# tl100-4-driver_sch-pcb.net
KiCad netlist of a schematic drawn in EAGLE
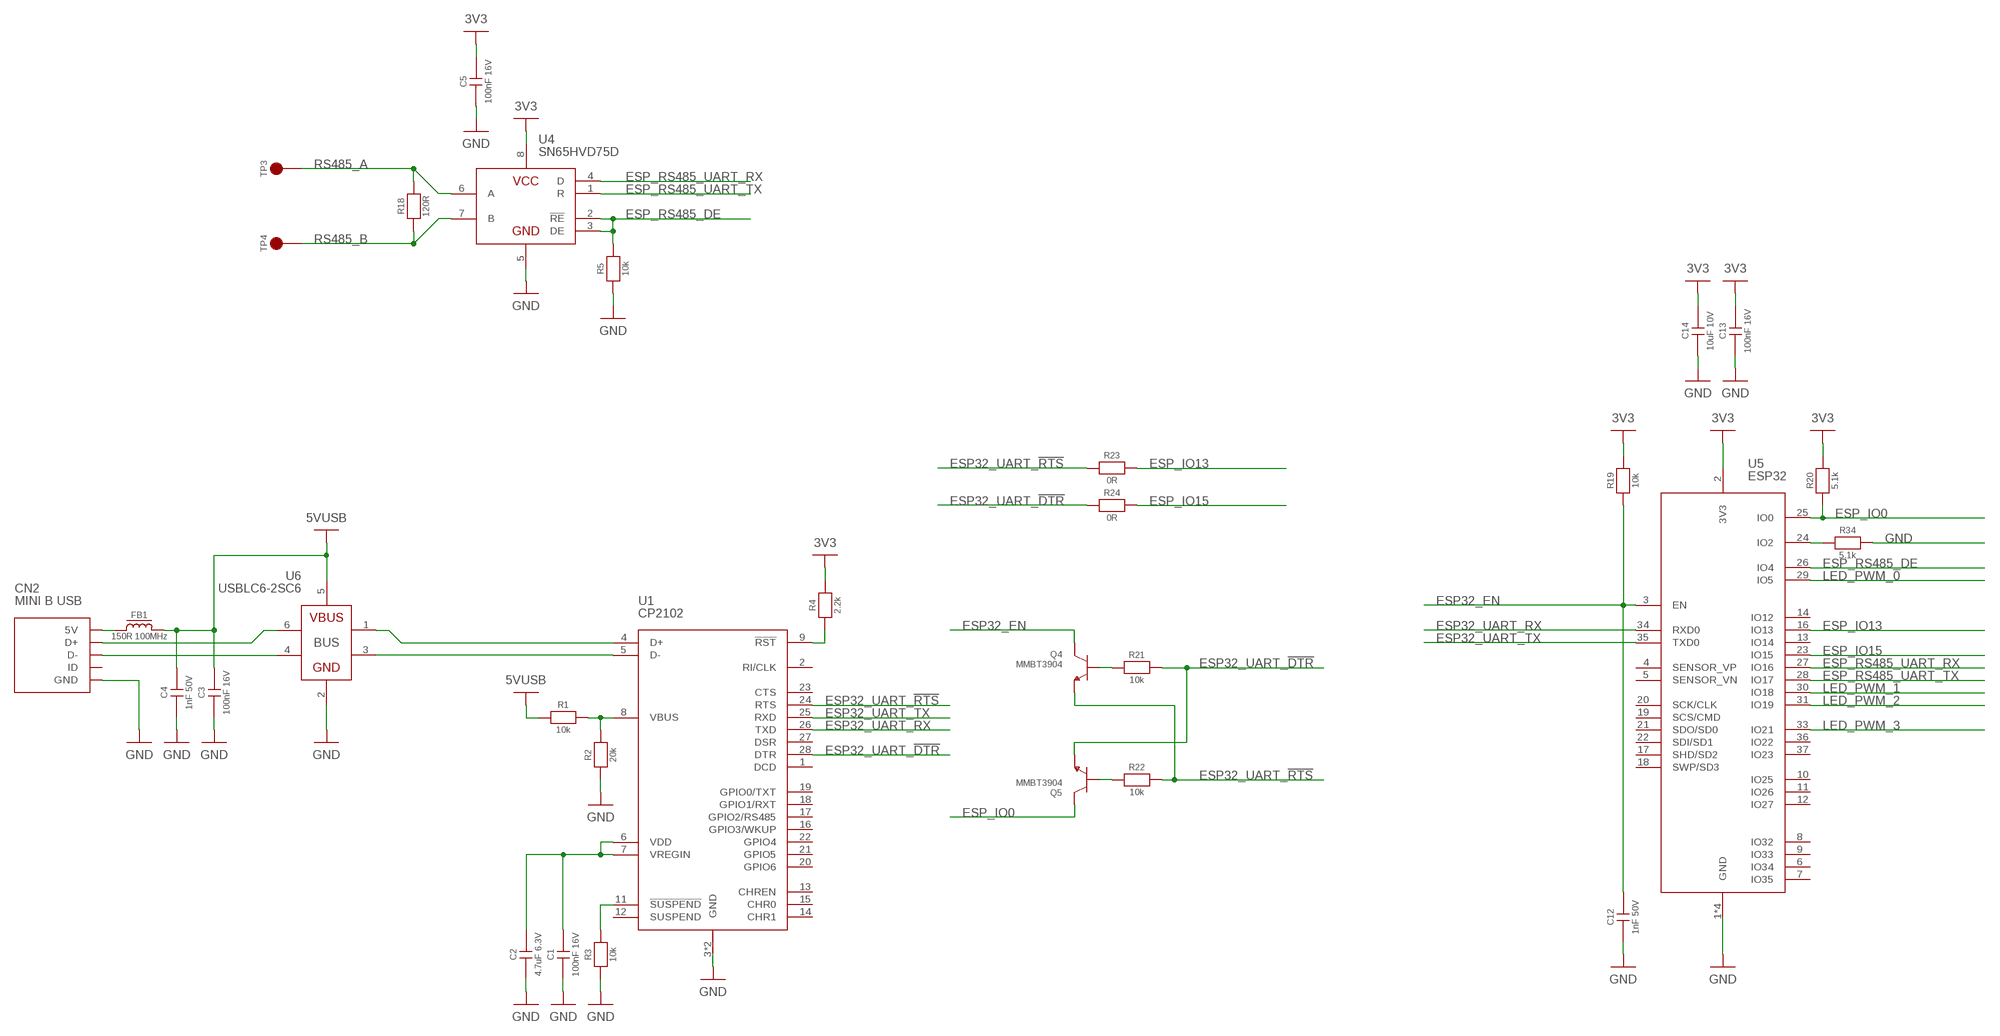
[diagram p0: schematic, sheet 1]
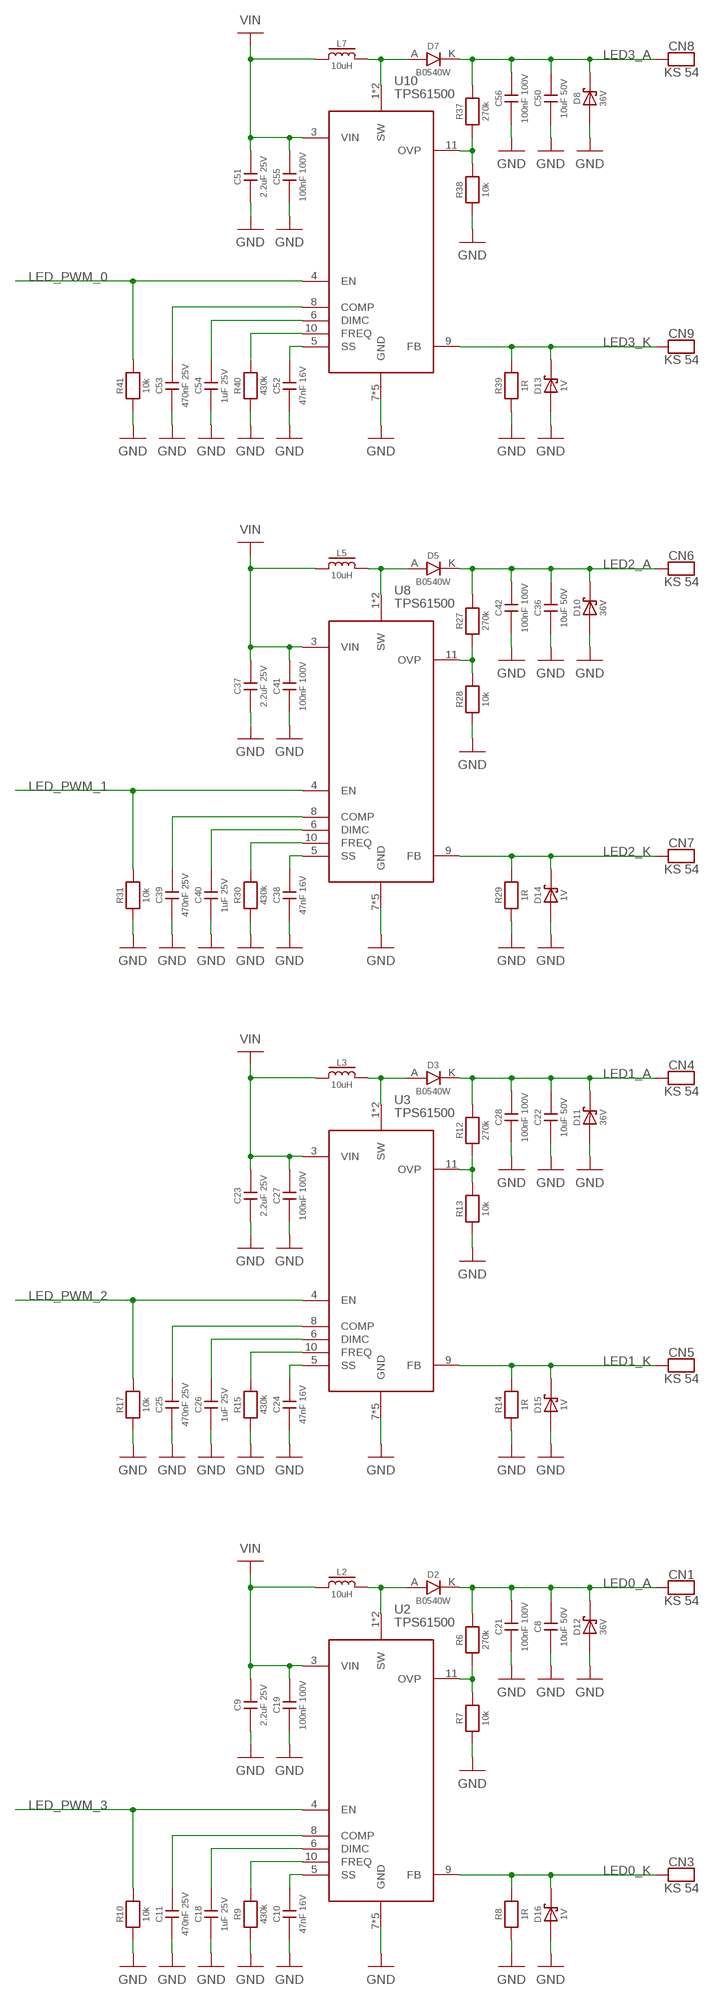
[diagram p1: schematic, sheet 2]
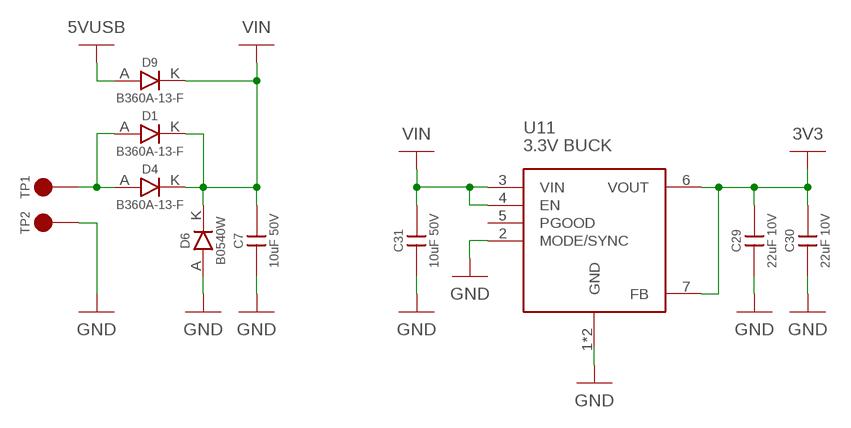
[diagram p2: schematic, sheet 3]
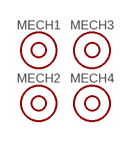
[diagram p3: schematic, sheet 4]

(export (version "E")
  (design (tool "Eeschema 10.0.6"))
  (components
    (comp (ref "MECH1")
      (value "6mm x 3mm")
      (footprint "eagle-import:MOUNTHOLE_6X3")
      (libsource (lib "eagle-import") (part "MOUNTHOLE"))
    )
    (comp (ref "MECH2")
      (value "6mm x 3mm")
      (footprint "eagle-import:MOUNTHOLE_6X3")
      (libsource (lib "eagle-import") (part "MOUNTHOLE"))
    )
    (comp (ref "MECH3")
      (value "6mm x 3mm")
      (footprint "eagle-import:MOUNTHOLE_6X3")
      (libsource (lib "eagle-import") (part "MOUNTHOLE"))
    )
    (comp (ref "MECH4")
      (value "6mm x 3mm")
      (footprint "eagle-import:MOUNTHOLE_6X3")
      (libsource (lib "eagle-import") (part "MOUNTHOLE"))
    )
    (comp (ref "C1")
      (value "100nF 16V")
      (footprint "eagle-import:0603")
      (libsource (lib "eagle-import") (part "CL10B104KO8WPNC"))
    )
    (comp (ref "C2")
      (value "4.7uF 6.3V")
      (footprint "eagle-import:0603")
      (libsource (lib "eagle-import") (part "GRM188R60J475ME19D"))
    )
    (comp (ref "C3")
      (value "100nF 16V")
      (footprint "eagle-import:0603")
      (libsource (lib "eagle-import") (part "CL10B104KO8WPNC"))
    )
    (comp (ref "C4")
      (value "1nF 50V")
      (footprint "eagle-import:0603")
      (libsource (lib "eagle-import") (part "CL10B102KB8NNNC"))
    )
    (comp (ref "C5")
      (value "100nF 16V")
      (footprint "eagle-import:0603")
      (libsource (lib "eagle-import") (part "CL10B104KO8WPNC"))
    )
    (comp (ref "C12")
      (value "1nF 50V")
      (footprint "eagle-import:0603")
      (libsource (lib "eagle-import") (part "CL10B102KB8NNNC"))
    )
    (comp (ref "C13")
      (value "100nF 16V")
      (footprint "eagle-import:0603")
      (libsource (lib "eagle-import") (part "CL10B104KO8WPNC"))
    )
    (comp (ref "C14")
      (value "10uF 10V")
      (footprint "eagle-import:0603")
      (libsource (lib "eagle-import") (part "GRM188R61A106KE69D"))
    )
    (comp (ref "CN2")
      (value "MINI B USB")
      (footprint "eagle-import:MUSB-05-S-B-SM-A")
      (libsource (lib "eagle-import") (part "MUSB-05-S-B-SM-A"))
    )
    (comp (ref "FB1")
      (value "150R 100MHz")
      (footprint "eagle-import:1206")
      (libsource (lib "eagle-import") (part "ILB1206ER151V"))
    )
    (comp (ref "Q4")
      (value "MMBT3904")
      (footprint "eagle-import:SOT23-3")
      (libsource (lib "eagle-import") (part "MMBT3904-7-F"))
    )
    (comp (ref "Q5")
      (value "MMBT3904")
      (footprint "eagle-import:SOT23-3")
      (libsource (lib "eagle-import") (part "MMBT3904-7-F"))
    )
    (comp (ref "R1")
      (value "10k")
      (footprint "eagle-import:0603")
      (libsource (lib "eagle-import") (part "ERJ3EKF1002V"))
    )
    (comp (ref "R2")
      (value "20k")
      (footprint "eagle-import:0603")
      (libsource (lib "eagle-import") (part "ERJ3EKF2002V"))
    )
    (comp (ref "R3")
      (value "10k")
      (footprint "eagle-import:0603")
      (libsource (lib "eagle-import") (part "ERJ3EKF1002V"))
    )
    (comp (ref "R4")
      (value "2.2k")
      (footprint "eagle-import:0603")
      (libsource (lib "eagle-import") (part "ERJ3EKF2201V"))
    )
    (comp (ref "R5")
      (value "10k")
      (footprint "eagle-import:0603")
      (libsource (lib "eagle-import") (part "ERJ3EKF1002V"))
    )
    (comp (ref "R18")
      (value "120R")
      (footprint "eagle-import:0603")
      (libsource (lib "eagle-import") (part "ERJ3EKF1200V"))
    )
    (comp (ref "R19")
      (value "10k")
      (footprint "eagle-import:0603")
      (libsource (lib "eagle-import") (part "ERJ3EKF1002V"))
    )
    (comp (ref "R20")
      (value "5.1k")
      (footprint "eagle-import:0603")
      (libsource (lib "eagle-import") (part "ERJ3EKF5101V"))
    )
    (comp (ref "R21")
      (value "10k")
      (footprint "eagle-import:0603")
      (libsource (lib "eagle-import") (part "ERJ3EKF1002V"))
    )
    (comp (ref "R22")
      (value "10k")
      (footprint "eagle-import:0603")
      (libsource (lib "eagle-import") (part "ERJ3EKF1002V"))
    )
    (comp (ref "R23")
      (value "0R")
      (footprint "eagle-import:0603")
      (libsource (lib "eagle-import") (part "CRCW06030000Z0EA"))
    )
    (comp (ref "R24")
      (value "0R")
      (footprint "eagle-import:0603")
      (libsource (lib "eagle-import") (part "CRCW06030000Z0EA"))
    )
    (comp (ref "R34")
      (value "5.1k")
      (footprint "eagle-import:0603")
      (libsource (lib "eagle-import") (part "ERJ3EKF5101V"))
    )
    (comp (ref "TP3")
      (value "2MM_TEST_POINT")
      (footprint "eagle-import:2MM_TEST_PAD")
      (libsource (lib "eagle-import") (part "2MM_TEST_POINT"))
    )
    (comp (ref "TP4")
      (value "2MM_TEST_POINT")
      (footprint "eagle-import:2MM_TEST_PAD")
      (libsource (lib "eagle-import") (part "2MM_TEST_POINT"))
    )
    (comp (ref "U1")
      (value "CP2102")
      (footprint "eagle-import:QFN28")
      (libsource (lib "eagle-import") (part "CP2102N-A01-GQFN28"))
    )
    (comp (ref "U4")
      (value "SN65HVD75D")
      (footprint "eagle-import:SO8")
      (libsource (lib "eagle-import") (part "SN65HVD75D"))
    )
    (comp (ref "U5")
      (value "ESP32")
      (footprint "eagle-import:ESP32-WROOM-32D")
      (libsource (lib "eagle-import") (part "ESP32-WROOM-32D"))
    )
    (comp (ref "U6")
      (value "USBLC6-2SC6")
      (footprint "eagle-import:SOT23-6")
      (libsource (lib "eagle-import") (part "USBLC6-2SC6"))
    )
    (comp (ref "C7")
      (value "10uF 50V")
      (footprint "eagle-import:1210")
      (libsource (lib "eagle-import") (part "C3225X7S1H106M250AB"))
    )
    (comp (ref "C29")
      (value "22uF 10V")
      (footprint "eagle-import:1206")
      (libsource (lib "eagle-import") (part "CL31B226MPHNNNE"))
    )
    (comp (ref "C30")
      (value "22uF 10V")
      (footprint "eagle-import:1206")
      (libsource (lib "eagle-import") (part "CL31B226MPHNNNE"))
    )
    (comp (ref "C31")
      (value "10uF 50V")
      (footprint "eagle-import:1210")
      (libsource (lib "eagle-import") (part "C3225X7S1H106M250AB"))
    )
    (comp (ref "D1")
      (value "B360A-13-F")
      (footprint "eagle-import:DO214AC")
      (libsource (lib "eagle-import") (part "B360A-13-F"))
    )
    (comp (ref "D4")
      (value "B360A-13-F")
      (footprint "eagle-import:DO214AC")
      (libsource (lib "eagle-import") (part "B360A-13-F"))
    )
    (comp (ref "D6")
      (value "B0540W")
      (footprint "eagle-import:SOD-123")
      (libsource (lib "eagle-import") (part "B0540W"))
    )
    (comp (ref "D9")
      (value "B360A-13-F")
      (footprint "eagle-import:DO214AC")
      (libsource (lib "eagle-import") (part "B360A-13-F"))
    )
    (comp (ref "TP1")
      (value "2MM_TEST_POINT")
      (footprint "eagle-import:2MM_TEST_PAD")
      (libsource (lib "eagle-import") (part "2MM_TEST_POINT"))
    )
    (comp (ref "TP2")
      (value "2MM_TEST_POINT")
      (footprint "eagle-import:2MM_TEST_PAD")
      (libsource (lib "eagle-import") (part "2MM_TEST_POINT"))
    )
    (comp (ref "U11")
      (value "3.3V BUCK")
      (footprint "eagle-import:TI_MICROSIP_10")
      (libsource (lib "eagle-import") (part "LMZM23600V3SILT"))
    )
    (comp (ref "C8")
      (value "10uF 50V")
      (footprint "eagle-import:1210")
      (libsource (lib "eagle-import") (part "C3225X7S1H106M250AB"))
    )
    (comp (ref "C9")
      (value "2.2uF 25V")
      (footprint "eagle-import:0603")
      (libsource (lib "eagle-import") (part "GRM188R61E225KA12D"))
    )
    (comp (ref "C10")
      (value "47nF 16V")
      (footprint "eagle-import:0603")
      (libsource (lib "eagle-import") (part "CL10B473KO8NNNC"))
    )
    (comp (ref "C11")
      (value "470nF 25V")
      (footprint "eagle-import:0603")
      (libsource (lib "eagle-import") (part "GRM188R71E474KA12D"))
    )
    (comp (ref "C18")
      (value "1uF 25V")
      (footprint "eagle-import:0603")
      (libsource (lib "eagle-import") (part "CL10A105KA8NNNC"))
    )
    (comp (ref "C19")
      (value "100nF 100V")
      (footprint "eagle-import:0603")
      (libsource (lib "eagle-import") (part "06031C104KAT2A"))
    )
    (comp (ref "C21")
      (value "100nF 100V")
      (footprint "eagle-import:0603")
      (libsource (lib "eagle-import") (part "06031C104KAT2A"))
    )
    (comp (ref "C22")
      (value "10uF 50V")
      (footprint "eagle-import:1210")
      (libsource (lib "eagle-import") (part "C3225X7S1H106M250AB"))
    )
    (comp (ref "C23")
      (value "2.2uF 25V")
      (footprint "eagle-import:0603")
      (libsource (lib "eagle-import") (part "GRM188R61E225KA12D"))
    )
    (comp (ref "C24")
      (value "47nF 16V")
      (footprint "eagle-import:0603")
      (libsource (lib "eagle-import") (part "CL10B473KO8NNNC"))
    )
    (comp (ref "C25")
      (value "470nF 25V")
      (footprint "eagle-import:0603")
      (libsource (lib "eagle-import") (part "GRM188R71E474KA12D"))
    )
    (comp (ref "C26")
      (value "1uF 25V")
      (footprint "eagle-import:0603")
      (libsource (lib "eagle-import") (part "CL10A105KA8NNNC"))
    )
    (comp (ref "C27")
      (value "100nF 100V")
      (footprint "eagle-import:0603")
      (libsource (lib "eagle-import") (part "06031C104KAT2A"))
    )
    (comp (ref "C28")
      (value "100nF 100V")
      (footprint "eagle-import:0603")
      (libsource (lib "eagle-import") (part "06031C104KAT2A"))
    )
    (comp (ref "C36")
      (value "10uF 50V")
      (footprint "eagle-import:1210")
      (libsource (lib "eagle-import") (part "C3225X7S1H106M250AB"))
    )
    (comp (ref "C37")
      (value "2.2uF 25V")
      (footprint "eagle-import:0603")
      (libsource (lib "eagle-import") (part "GRM188R61E225KA12D"))
    )
    (comp (ref "C38")
      (value "47nF 16V")
      (footprint "eagle-import:0603")
      (libsource (lib "eagle-import") (part "CL10B473KO8NNNC"))
    )
    (comp (ref "C39")
      (value "470nF 25V")
      (footprint "eagle-import:0603")
      (libsource (lib "eagle-import") (part "GRM188R71E474KA12D"))
    )
    (comp (ref "C40")
      (value "1uF 25V")
      (footprint "eagle-import:0603")
      (libsource (lib "eagle-import") (part "CL10A105KA8NNNC"))
    )
    (comp (ref "C41")
      (value "100nF 100V")
      (footprint "eagle-import:0603")
      (libsource (lib "eagle-import") (part "06031C104KAT2A"))
    )
    (comp (ref "C42")
      (value "100nF 100V")
      (footprint "eagle-import:0603")
      (libsource (lib "eagle-import") (part "06031C104KAT2A"))
    )
    (comp (ref "C50")
      (value "10uF 50V")
      (footprint "eagle-import:1210")
      (libsource (lib "eagle-import") (part "C3225X7S1H106M250AB"))
    )
    (comp (ref "C51")
      (value "2.2uF 25V")
      (footprint "eagle-import:0603")
      (libsource (lib "eagle-import") (part "GRM188R61E225KA12D"))
    )
    (comp (ref "C52")
      (value "47nF 16V")
      (footprint "eagle-import:0603")
      (libsource (lib "eagle-import") (part "CL10B473KO8NNNC"))
    )
    (comp (ref "C53")
      (value "470nF 25V")
      (footprint "eagle-import:0603")
      (libsource (lib "eagle-import") (part "GRM188R71E474KA12D"))
    )
    (comp (ref "C54")
      (value "1uF 25V")
      (footprint "eagle-import:0603")
      (libsource (lib "eagle-import") (part "CL10A105KA8NNNC"))
    )
    (comp (ref "C55")
      (value "100nF 100V")
      (footprint "eagle-import:0603")
      (libsource (lib "eagle-import") (part "06031C104KAT2A"))
    )
    (comp (ref "C56")
      (value "100nF 100V")
      (footprint "eagle-import:0603")
      (libsource (lib "eagle-import") (part "06031C104KAT2A"))
    )
    (comp (ref "CN1")
      (value "KS 54")
      (footprint "eagle-import:KEYSTONE_54")
      (libsource (lib "eagle-import") (part "KEYSTONE_54"))
    )
    (comp (ref "CN3")
      (value "KS 54")
      (footprint "eagle-import:KEYSTONE_54")
      (libsource (lib "eagle-import") (part "KEYSTONE_54"))
    )
    (comp (ref "CN4")
      (value "KS 54")
      (footprint "eagle-import:KEYSTONE_54")
      (libsource (lib "eagle-import") (part "KEYSTONE_54"))
    )
    (comp (ref "CN5")
      (value "KS 54")
      (footprint "eagle-import:KEYSTONE_54")
      (libsource (lib "eagle-import") (part "KEYSTONE_54"))
    )
    (comp (ref "CN6")
      (value "KS 54")
      (footprint "eagle-import:KEYSTONE_54")
      (libsource (lib "eagle-import") (part "KEYSTONE_54"))
    )
    (comp (ref "CN7")
      (value "KS 54")
      (footprint "eagle-import:KEYSTONE_54")
      (libsource (lib "eagle-import") (part "KEYSTONE_54"))
    )
    (comp (ref "CN8")
      (value "KS 54")
      (footprint "eagle-import:KEYSTONE_54")
      (libsource (lib "eagle-import") (part "KEYSTONE_54"))
    )
    (comp (ref "CN9")
      (value "KS 54")
      (footprint "eagle-import:KEYSTONE_54")
      (libsource (lib "eagle-import") (part "KEYSTONE_54"))
    )
    (comp (ref "D2")
      (value "B0540W")
      (footprint "eagle-import:SOD-123")
      (libsource (lib "eagle-import") (part "B0540W"))
    )
    (comp (ref "D3")
      (value "B0540W")
      (footprint "eagle-import:SOD-123")
      (libsource (lib "eagle-import") (part "B0540W"))
    )
    (comp (ref "D5")
      (value "B0540W")
      (footprint "eagle-import:SOD-123")
      (libsource (lib "eagle-import") (part "B0540W"))
    )
    (comp (ref "D7")
      (value "B0540W")
      (footprint "eagle-import:SOD-123")
      (libsource (lib "eagle-import") (part "B0540W"))
    )
    (comp (ref "D8")
      (value "36V")
      (footprint "eagle-import:SOT23-3")
      (libsource (lib "eagle-import") (part "GSOT36-HE3-08"))
    )
    (comp (ref "D10")
      (value "36V")
      (footprint "eagle-import:SOT23-3")
      (libsource (lib "eagle-import") (part "GSOT36-HE3-08"))
    )
    (comp (ref "D11")
      (value "36V")
      (footprint "eagle-import:SOT23-3")
      (libsource (lib "eagle-import") (part "GSOT36-HE3-08"))
    )
    (comp (ref "D12")
      (value "36V")
      (footprint "eagle-import:SOT23-3")
      (libsource (lib "eagle-import") (part "GSOT36-HE3-08"))
    )
    (comp (ref "D13")
      (value "1V")
      (footprint "eagle-import:SC-79")
      (libsource (lib "eagle-import") (part "VESD01C1-02VHG3-08"))
    )
    (comp (ref "D14")
      (value "1V")
      (footprint "eagle-import:SC-79")
      (libsource (lib "eagle-import") (part "VESD01C1-02VHG3-08"))
    )
    (comp (ref "D15")
      (value "1V")
      (footprint "eagle-import:SC-79")
      (libsource (lib "eagle-import") (part "VESD01C1-02VHG3-08"))
    )
    (comp (ref "D16")
      (value "1V")
      (footprint "eagle-import:SC-79")
      (libsource (lib "eagle-import") (part "VESD01C1-02VHG3-08"))
    )
    (comp (ref "L2")
      (value "10uH")
      (footprint "eagle-import:SRN6045")
      (libsource (lib "eagle-import") (part "SRN6045-100M"))
    )
    (comp (ref "L3")
      (value "10uH")
      (footprint "eagle-import:SRN6045")
      (libsource (lib "eagle-import") (part "SRN6045-100M"))
    )
    (comp (ref "L5")
      (value "10uH")
      (footprint "eagle-import:SRN6045")
      (libsource (lib "eagle-import") (part "SRN6045-100M"))
    )
    (comp (ref "L7")
      (value "10uH")
      (footprint "eagle-import:SRN6045")
      (libsource (lib "eagle-import") (part "SRN6045-100M"))
    )
    (comp (ref "R6")
      (value "270k")
      (footprint "eagle-import:0603")
      (libsource (lib "eagle-import") (part "ERJ3EKF2703V"))
    )
    (comp (ref "R7")
      (value "10k")
      (footprint "eagle-import:0603")
      (libsource (lib "eagle-import") (part "ERJ3EKF1002V"))
    )
    (comp (ref "R8")
      (value "1R")
      (footprint "eagle-import:1206")
      (libsource (lib "eagle-import") (part "CRCW12061R00FKEA"))
    )
    (comp (ref "R9")
      (value "430k")
      (footprint "eagle-import:0603")
      (libsource (lib "eagle-import") (part "ERJ3EKF4303V"))
    )
    (comp (ref "R10")
      (value "10k")
      (footprint "eagle-import:0603")
      (libsource (lib "eagle-import") (part "ERJ3EKF1002V"))
    )
    (comp (ref "R12")
      (value "270k")
      (footprint "eagle-import:0603")
      (libsource (lib "eagle-import") (part "ERJ3EKF2703V"))
    )
    (comp (ref "R13")
      (value "10k")
      (footprint "eagle-import:0603")
      (libsource (lib "eagle-import") (part "ERJ3EKF1002V"))
    )
    (comp (ref "R14")
      (value "1R")
      (footprint "eagle-import:1206")
      (libsource (lib "eagle-import") (part "CRCW12061R00FKEA"))
    )
    (comp (ref "R15")
      (value "430k")
      (footprint "eagle-import:0603")
      (libsource (lib "eagle-import") (part "ERJ3EKF4303V"))
    )
    (comp (ref "R17")
      (value "10k")
      (footprint "eagle-import:0603")
      (libsource (lib "eagle-import") (part "ERJ3EKF1002V"))
    )
    (comp (ref "R27")
      (value "270k")
      (footprint "eagle-import:0603")
      (libsource (lib "eagle-import") (part "ERJ3EKF2703V"))
    )
    (comp (ref "R28")
      (value "10k")
      (footprint "eagle-import:0603")
      (libsource (lib "eagle-import") (part "ERJ3EKF1002V"))
    )
    (comp (ref "R29")
      (value "1R")
      (footprint "eagle-import:1206")
      (libsource (lib "eagle-import") (part "CRCW12061R00FKEA"))
    )
    (comp (ref "R30")
      (value "430k")
      (footprint "eagle-import:0603")
      (libsource (lib "eagle-import") (part "ERJ3EKF4303V"))
    )
    (comp (ref "R31")
      (value "10k")
      (footprint "eagle-import:0603")
      (libsource (lib "eagle-import") (part "ERJ3EKF1002V"))
    )
    (comp (ref "R37")
      (value "270k")
      (footprint "eagle-import:0603")
      (libsource (lib "eagle-import") (part "ERJ3EKF2703V"))
    )
    (comp (ref "R38")
      (value "10k")
      (footprint "eagle-import:0603")
      (libsource (lib "eagle-import") (part "ERJ3EKF1002V"))
    )
    (comp (ref "R39")
      (value "1R")
      (footprint "eagle-import:1206")
      (libsource (lib "eagle-import") (part "CRCW12061R00FKEA"))
    )
    (comp (ref "R40")
      (value "430k")
      (footprint "eagle-import:0603")
      (libsource (lib "eagle-import") (part "ERJ3EKF4303V"))
    )
    (comp (ref "R41")
      (value "10k")
      (footprint "eagle-import:0603")
      (libsource (lib "eagle-import") (part "ERJ3EKF1002V"))
    )
    (comp (ref "U2")
      (value "TPS61500")
      (footprint "eagle-import:HTSSOP14-4.5")
      (libsource (lib "eagle-import") (part "TPS61500"))
    )
    (comp (ref "U3")
      (value "TPS61500")
      (footprint "eagle-import:HTSSOP14-4.5")
      (libsource (lib "eagle-import") (part "TPS61500"))
    )
    (comp (ref "U8")
      (value "TPS61500")
      (footprint "eagle-import:HTSSOP14-4.5")
      (libsource (lib "eagle-import") (part "TPS61500"))
    )
    (comp (ref "U10")
      (value "TPS61500")
      (footprint "eagle-import:HTSSOP14-4.5")
      (libsource (lib "eagle-import") (part "TPS61500"))
    )
  )
  (nets
    (net (code "1") (name "3V3") (class "Default")
      (node (ref "C13") (pin "2") (pinfunction "2_2") (pintype "bidirectional"))
      (node (ref "C14") (pin "2") (pinfunction "2_2") (pintype "bidirectional"))
      (node (ref "C29") (pin "2") (pinfunction "2_2") (pintype "bidirectional"))
      (node (ref "C30") (pin "2") (pinfunction "2_2") (pintype "bidirectional"))
      (node (ref "C5") (pin "2") (pinfunction "2_2") (pintype "bidirectional"))
      (node (ref "R19") (pin "2") (pinfunction "2_2") (pintype "bidirectional"))
      (node (ref "R20") (pin "2") (pinfunction "2_2") (pintype "bidirectional"))
      (node (ref "R4") (pin "2") (pinfunction "2_2") (pintype "bidirectional"))
      (node (ref "U11") (pin "6") (pinfunction "VOUT_6") (pintype "bidirectional"))
      (node (ref "U11") (pin "7") (pinfunction "FB_7") (pintype "bidirectional"))
      (node (ref "U4") (pin "8") (pinfunction "VCC_8") (pintype "bidirectional"))
      (node (ref "U5") (pin "2") (pinfunction "3V3_2") (pintype "bidirectional"))
    )
    (net (code "2") (name "5VUSB") (class "Default")
      (node (ref "C3") (pin "2") (pinfunction "2_2") (pintype "bidirectional"))
      (node (ref "C4") (pin "2") (pinfunction "2_2") (pintype "bidirectional"))
      (node (ref "D9") (pin "A") (pinfunction "A_A") (pintype "bidirectional"))
      (node (ref "FB1") (pin "2") (pinfunction "2_2") (pintype "bidirectional"))
      (node (ref "R1") (pin "1") (pinfunction "1_1") (pintype "bidirectional"))
      (node (ref "U6") (pin "5") (pinfunction "VBUS_5") (pintype "bidirectional"))
    )
    (net (code "3") (name "ESP32_EN") (class "Default")
      (node (ref "C12") (pin "2") (pinfunction "2_2") (pintype "bidirectional"))
      (node (ref "Q4") (pin "2") (pinfunction "C_2") (pintype "bidirectional"))
      (node (ref "R19") (pin "1") (pinfunction "1_1") (pintype "bidirectional"))
      (node (ref "U5") (pin "3") (pinfunction "EN_3") (pintype "bidirectional"))
    )
    (net (code "4") (name "ESP32_UART_RX") (class "Default")
      (node (ref "U1") (pin "26") (pinfunction "TXD_26") (pintype "bidirectional"))
      (node (ref "U5") (pin "34") (pinfunction "RXD0_34") (pintype "bidirectional"))
    )
    (net (code "5") (name "ESP32_UART_TX") (class "Default")
      (node (ref "U1") (pin "25") (pinfunction "RXD_25") (pintype "bidirectional"))
      (node (ref "U5") (pin "35") (pinfunction "TXD0_35") (pintype "bidirectional"))
    )
    (net (code "6") (name "ESP32_UART_~{DTR}") (class "Default")
      (node (ref "Q5") (pin "3") (pinfunction "E_3") (pintype "bidirectional"))
      (node (ref "R21") (pin "2") (pinfunction "2_2") (pintype "bidirectional"))
      (node (ref "R24") (pin "1") (pinfunction "1_1") (pintype "bidirectional"))
      (node (ref "U1") (pin "28") (pinfunction "DTR_28") (pintype "bidirectional"))
    )
    (net (code "7") (name "ESP32_UART_~{RTS}") (class "Default")
      (node (ref "Q4") (pin "3") (pinfunction "E_3") (pintype "bidirectional"))
      (node (ref "R22") (pin "2") (pinfunction "2_2") (pintype "bidirectional"))
      (node (ref "R23") (pin "1") (pinfunction "1_1") (pintype "bidirectional"))
      (node (ref "U1") (pin "24") (pinfunction "RTS_24") (pintype "bidirectional"))
    )
    (net (code "8") (name "ESP_IO0") (class "Default")
      (node (ref "Q5") (pin "2") (pinfunction "C_2") (pintype "bidirectional"))
      (node (ref "R20") (pin "1") (pinfunction "1_1") (pintype "bidirectional"))
      (node (ref "U5") (pin "25") (pinfunction "IO0_25") (pintype "bidirectional"))
    )
    (net (code "9") (name "ESP_IO13") (class "Default")
      (node (ref "R23") (pin "2") (pinfunction "2_2") (pintype "bidirectional"))
      (node (ref "U5") (pin "16") (pinfunction "IO13_16") (pintype "bidirectional"))
    )
    (net (code "10") (name "ESP_IO15") (class "Default")
      (node (ref "R24") (pin "2") (pinfunction "2_2") (pintype "bidirectional"))
      (node (ref "U5") (pin "23") (pinfunction "IO15_23") (pintype "bidirectional"))
    )
    (net (code "11") (name "ESP_RS485_DE") (class "Default")
      (node (ref "R5") (pin "2") (pinfunction "2_2") (pintype "bidirectional"))
      (node (ref "U4") (pin "2") (pinfunction "~{RE}_2") (pintype "bidirectional"))
      (node (ref "U4") (pin "3") (pinfunction "DE_3") (pintype "bidirectional"))
      (node (ref "U5") (pin "26") (pinfunction "IO4_26") (pintype "bidirectional"))
    )
    (net (code "12") (name "ESP_RS485_UART_RX") (class "Default")
      (node (ref "U4") (pin "4") (pinfunction "D_4") (pintype "bidirectional"))
      (node (ref "U5") (pin "27") (pinfunction "IO16_27") (pintype "bidirectional"))
    )
    (net (code "13") (name "ESP_RS485_UART_TX") (class "Default")
      (node (ref "U4") (pin "1") (pinfunction "R_1") (pintype "bidirectional"))
      (node (ref "U5") (pin "28") (pinfunction "IO17_28") (pintype "bidirectional"))
    )
    (net (code "14") (name "GND") (class "Default")
      (node (ref "C1") (pin "1") (pinfunction "1_1") (pintype "bidirectional"))
      (node (ref "C10") (pin "1") (pinfunction "1_1") (pintype "bidirectional"))
      (node (ref "C11") (pin "1") (pinfunction "1_1") (pintype "bidirectional"))
      (node (ref "C12") (pin "1") (pinfunction "1_1") (pintype "bidirectional"))
      (node (ref "C13") (pin "1") (pinfunction "1_1") (pintype "bidirectional"))
      (node (ref "C14") (pin "1") (pinfunction "1_1") (pintype "bidirectional"))
      (node (ref "C18") (pin "1") (pinfunction "1_1") (pintype "bidirectional"))
      (node (ref "C19") (pin "1") (pinfunction "1_1") (pintype "bidirectional"))
      (node (ref "C2") (pin "1") (pinfunction "1_1") (pintype "bidirectional"))
      (node (ref "C21") (pin "1") (pinfunction "1_1") (pintype "bidirectional"))
      (node (ref "C22") (pin "1") (pinfunction "1_1") (pintype "bidirectional"))
      (node (ref "C23") (pin "1") (pinfunction "1_1") (pintype "bidirectional"))
      (node (ref "C24") (pin "1") (pinfunction "1_1") (pintype "bidirectional"))
      (node (ref "C25") (pin "1") (pinfunction "1_1") (pintype "bidirectional"))
      (node (ref "C26") (pin "1") (pinfunction "1_1") (pintype "bidirectional"))
      (node (ref "C27") (pin "1") (pinfunction "1_1") (pintype "bidirectional"))
      (node (ref "C28") (pin "1") (pinfunction "1_1") (pintype "bidirectional"))
      (node (ref "C29") (pin "1") (pinfunction "1_1") (pintype "bidirectional"))
      (node (ref "C3") (pin "1") (pinfunction "1_1") (pintype "bidirectional"))
      (node (ref "C30") (pin "1") (pinfunction "1_1") (pintype "bidirectional"))
      (node (ref "C31") (pin "1") (pinfunction "1_1") (pintype "bidirectional"))
      (node (ref "C36") (pin "1") (pinfunction "1_1") (pintype "bidirectional"))
      (node (ref "C37") (pin "1") (pinfunction "1_1") (pintype "bidirectional"))
      (node (ref "C38") (pin "1") (pinfunction "1_1") (pintype "bidirectional"))
      (node (ref "C39") (pin "1") (pinfunction "1_1") (pintype "bidirectional"))
      (node (ref "C4") (pin "1") (pinfunction "1_1") (pintype "bidirectional"))
      (node (ref "C40") (pin "1") (pinfunction "1_1") (pintype "bidirectional"))
      (node (ref "C41") (pin "1") (pinfunction "1_1") (pintype "bidirectional"))
      (node (ref "C42") (pin "1") (pinfunction "1_1") (pintype "bidirectional"))
      (node (ref "C5") (pin "1") (pinfunction "1_1") (pintype "bidirectional"))
      (node (ref "C50") (pin "1") (pinfunction "1_1") (pintype "bidirectional"))
      (node (ref "C51") (pin "1") (pinfunction "1_1") (pintype "bidirectional"))
      (node (ref "C52") (pin "1") (pinfunction "1_1") (pintype "bidirectional"))
      (node (ref "C53") (pin "1") (pinfunction "1_1") (pintype "bidirectional"))
      (node (ref "C54") (pin "1") (pinfunction "1_1") (pintype "bidirectional"))
      (node (ref "C55") (pin "1") (pinfunction "1_1") (pintype "bidirectional"))
      (node (ref "C56") (pin "1") (pinfunction "1_1") (pintype "bidirectional"))
      (node (ref "C7") (pin "1") (pinfunction "1_1") (pintype "bidirectional"))
      (node (ref "C8") (pin "1") (pinfunction "1_1") (pintype "bidirectional"))
      (node (ref "C9") (pin "1") (pinfunction "1_1") (pintype "bidirectional"))
      (node (ref "CN2") (pin "GND") (pinfunction "GND_GND") (pintype "bidirectional"))
      (node (ref "CN2") (pin "SHIELD1") (pinfunction "GND_SHIELD1") (pintype "bidirectional"))
      (node (ref "CN2") (pin "SHIELD2") (pinfunction "GND_SHIELD2") (pintype "bidirectional"))
      (node (ref "CN2") (pin "SHIELD3") (pinfunction "GND_SHIELD3") (pintype "bidirectional"))
      (node (ref "CN2") (pin "SHIELD4") (pinfunction "GND_SHIELD4") (pintype "bidirectional"))
      (node (ref "D10") (pin "1") (pinfunction "A_1") (pintype "bidirectional"))
      (node (ref "D11") (pin "1") (pinfunction "A_1") (pintype "bidirectional"))
      (node (ref "D12") (pin "1") (pinfunction "A_1") (pintype "bidirectional"))
      (node (ref "D13") (pin "A") (pinfunction "A_A") (pintype "bidirectional"))
      (node (ref "D14") (pin "A") (pinfunction "A_A") (pintype "bidirectional"))
      (node (ref "D15") (pin "A") (pinfunction "A_A") (pintype "bidirectional"))
      (node (ref "D16") (pin "A") (pinfunction "A_A") (pintype "bidirectional"))
      (node (ref "D6") (pin "A") (pinfunction "A_A") (pintype "bidirectional"))
      (node (ref "D8") (pin "1") (pinfunction "A_1") (pintype "bidirectional"))
      (node (ref "R10") (pin "1") (pinfunction "1_1") (pintype "bidirectional"))
      (node (ref "R13") (pin "1") (pinfunction "1_1") (pintype "bidirectional"))
      (node (ref "R14") (pin "1") (pinfunction "1_1") (pintype "bidirectional"))
      (node (ref "R15") (pin "1") (pinfunction "1_1") (pintype "bidirectional"))
      (node (ref "R17") (pin "1") (pinfunction "1_1") (pintype "bidirectional"))
      (node (ref "R2") (pin "1") (pinfunction "1_1") (pintype "bidirectional"))
      (node (ref "R28") (pin "1") (pinfunction "1_1") (pintype "bidirectional"))
      (node (ref "R29") (pin "1") (pinfunction "1_1") (pintype "bidirectional"))
      (node (ref "R3") (pin "1") (pinfunction "1_1") (pintype "bidirectional"))
      (node (ref "R30") (pin "1") (pinfunction "1_1") (pintype "bidirectional"))
      (node (ref "R31") (pin "1") (pinfunction "1_1") (pintype "bidirectional"))
      (node (ref "R34") (pin "2") (pinfunction "2_2") (pintype "bidirectional"))
      (node (ref "R38") (pin "1") (pinfunction "1_1") (pintype "bidirectional"))
      (node (ref "R39") (pin "1") (pinfunction "1_1") (pintype "bidirectional"))
      (node (ref "R40") (pin "1") (pinfunction "1_1") (pintype "bidirectional"))
      (node (ref "R41") (pin "1") (pinfunction "1_1") (pintype "bidirectional"))
      (node (ref "R5") (pin "1") (pinfunction "1_1") (pintype "bidirectional"))
      (node (ref "R7") (pin "1") (pinfunction "1_1") (pintype "bidirectional"))
      (node (ref "R8") (pin "1") (pinfunction "1_1") (pintype "bidirectional"))
      (node (ref "R9") (pin "1") (pinfunction "1_1") (pintype "bidirectional"))
      (node (ref "TP2") (pin "1") (pinfunction "P$1_1") (pintype "bidirectional"))
      (node (ref "U1") (pin "29") (pinfunction "GND_29") (pintype "bidirectional"))
      (node (ref "U1") (pin "3") (pinfunction "GND_3") (pintype "bidirectional"))
      (node (ref "U10") (pin "12") (pinfunction "GND_12") (pintype "bidirectional"))
      (node (ref "U10") (pin "13") (pinfunction "GND_13") (pintype "bidirectional"))
      (node (ref "U10") (pin "14") (pinfunction "GND_14") (pintype "bidirectional"))
      (node (ref "U10") (pin "7") (pinfunction "GND_7") (pintype "bidirectional"))
      (node (ref "U10") (pin "PAD") (pinfunction "GND_PAD") (pintype "bidirectional"))
      (node (ref "U11") (pin "1") (pinfunction "GND_1") (pintype "bidirectional"))
      (node (ref "U11") (pin "2") (pinfunction "MODE/SYNC_2") (pintype "bidirectional"))
      (node (ref "U11") (pin "PAD") (pinfunction "GND_PAD") (pintype "bidirectional"))
      (node (ref "U2") (pin "12") (pinfunction "GND_12") (pintype "bidirectional"))
      (node (ref "U2") (pin "13") (pinfunction "GND_13") (pintype "bidirectional"))
      (node (ref "U2") (pin "14") (pinfunction "GND_14") (pintype "bidirectional"))
      (node (ref "U2") (pin "7") (pinfunction "GND_7") (pintype "bidirectional"))
      (node (ref "U2") (pin "PAD") (pinfunction "GND_PAD") (pintype "bidirectional"))
      (node (ref "U3") (pin "12") (pinfunction "GND_12") (pintype "bidirectional"))
      (node (ref "U3") (pin "13") (pinfunction "GND_13") (pintype "bidirectional"))
      (node (ref "U3") (pin "14") (pinfunction "GND_14") (pintype "bidirectional"))
      (node (ref "U3") (pin "7") (pinfunction "GND_7") (pintype "bidirectional"))
      (node (ref "U3") (pin "PAD") (pinfunction "GND_PAD") (pintype "bidirectional"))
      (node (ref "U4") (pin "5") (pinfunction "GND_5") (pintype "bidirectional"))
      (node (ref "U5") (pin "1") (pinfunction "GND_1") (pintype "bidirectional"))
      (node (ref "U5") (pin "15") (pinfunction "GND_15") (pintype "bidirectional"))
      (node (ref "U5") (pin "38") (pinfunction "GND_38") (pintype "bidirectional"))
      (node (ref "U5") (pin "39") (pinfunction "GND_39") (pintype "bidirectional"))
      (node (ref "U6") (pin "2") (pinfunction "GND_2") (pintype "bidirectional"))
      (node (ref "U8") (pin "12") (pinfunction "GND_12") (pintype "bidirectional"))
      (node (ref "U8") (pin "13") (pinfunction "GND_13") (pintype "bidirectional"))
      (node (ref "U8") (pin "14") (pinfunction "GND_14") (pintype "bidirectional"))
      (node (ref "U8") (pin "7") (pinfunction "GND_7") (pintype "bidirectional"))
      (node (ref "U8") (pin "PAD") (pinfunction "GND_PAD") (pintype "bidirectional"))
    )
    (net (code "15") (name "LED0_A") (class "Default")
      (node (ref "C21") (pin "2") (pinfunction "2_2") (pintype "bidirectional"))
      (node (ref "C8") (pin "2") (pinfunction "2_2") (pintype "bidirectional"))
      (node (ref "CN1") (pin "P$1") (pinfunction "P$1_P$1") (pintype "bidirectional"))
      (node (ref "CN1") (pin "P$2") (pinfunction "P$1_P$2") (pintype "bidirectional"))
      (node (ref "CN1") (pin "P$3") (pinfunction "P$1_P$3") (pintype "bidirectional"))
      (node (ref "D12") (pin "2") (pinfunction "K_2") (pintype "bidirectional"))
      (node (ref "D2") (pin "K") (pinfunction "K_K") (pintype "bidirectional"))
      (node (ref "R6") (pin "2") (pinfunction "2_2") (pintype "bidirectional"))
    )
    (net (code "16") (name "LED0_K") (class "Default")
      (node (ref "CN3") (pin "P$1") (pinfunction "P$1_P$1") (pintype "bidirectional"))
      (node (ref "CN3") (pin "P$2") (pinfunction "P$1_P$2") (pintype "bidirectional"))
      (node (ref "CN3") (pin "P$3") (pinfunction "P$1_P$3") (pintype "bidirectional"))
      (node (ref "D16") (pin "K") (pinfunction "K_K") (pintype "bidirectional"))
      (node (ref "R8") (pin "2") (pinfunction "2_2") (pintype "bidirectional"))
      (node (ref "U2") (pin "9") (pinfunction "FB_9") (pintype "bidirectional"))
    )
    (net (code "17") (name "LED1_A") (class "Default")
      (node (ref "C22") (pin "2") (pinfunction "2_2") (pintype "bidirectional"))
      (node (ref "C28") (pin "2") (pinfunction "2_2") (pintype "bidirectional"))
      (node (ref "CN4") (pin "P$1") (pinfunction "P$1_P$1") (pintype "bidirectional"))
      (node (ref "CN4") (pin "P$2") (pinfunction "P$1_P$2") (pintype "bidirectional"))
      (node (ref "CN4") (pin "P$3") (pinfunction "P$1_P$3") (pintype "bidirectional"))
      (node (ref "D11") (pin "2") (pinfunction "K_2") (pintype "bidirectional"))
      (node (ref "D3") (pin "K") (pinfunction "K_K") (pintype "bidirectional"))
      (node (ref "R12") (pin "2") (pinfunction "2_2") (pintype "bidirectional"))
    )
    (net (code "18") (name "LED1_K") (class "Default")
      (node (ref "CN5") (pin "P$1") (pinfunction "P$1_P$1") (pintype "bidirectional"))
      (node (ref "CN5") (pin "P$2") (pinfunction "P$1_P$2") (pintype "bidirectional"))
      (node (ref "CN5") (pin "P$3") (pinfunction "P$1_P$3") (pintype "bidirectional"))
      (node (ref "D15") (pin "K") (pinfunction "K_K") (pintype "bidirectional"))
      (node (ref "R14") (pin "2") (pinfunction "2_2") (pintype "bidirectional"))
      (node (ref "U3") (pin "9") (pinfunction "FB_9") (pintype "bidirectional"))
    )
    (net (code "19") (name "LED2_A") (class "Default")
      (node (ref "C36") (pin "2") (pinfunction "2_2") (pintype "bidirectional"))
      (node (ref "C42") (pin "2") (pinfunction "2_2") (pintype "bidirectional"))
      (node (ref "CN6") (pin "P$1") (pinfunction "P$1_P$1") (pintype "bidirectional"))
      (node (ref "CN6") (pin "P$2") (pinfunction "P$1_P$2") (pintype "bidirectional"))
      (node (ref "CN6") (pin "P$3") (pinfunction "P$1_P$3") (pintype "bidirectional"))
      (node (ref "D10") (pin "2") (pinfunction "K_2") (pintype "bidirectional"))
      (node (ref "D5") (pin "K") (pinfunction "K_K") (pintype "bidirectional"))
      (node (ref "R27") (pin "2") (pinfunction "2_2") (pintype "bidirectional"))
    )
    (net (code "20") (name "LED2_K") (class "Default")
      (node (ref "CN7") (pin "P$1") (pinfunction "P$1_P$1") (pintype "bidirectional"))
      (node (ref "CN7") (pin "P$2") (pinfunction "P$1_P$2") (pintype "bidirectional"))
      (node (ref "CN7") (pin "P$3") (pinfunction "P$1_P$3") (pintype "bidirectional"))
      (node (ref "D14") (pin "K") (pinfunction "K_K") (pintype "bidirectional"))
      (node (ref "R29") (pin "2") (pinfunction "2_2") (pintype "bidirectional"))
      (node (ref "U8") (pin "9") (pinfunction "FB_9") (pintype "bidirectional"))
    )
    (net (code "21") (name "LED3_A") (class "Default")
      (node (ref "C50") (pin "2") (pinfunction "2_2") (pintype "bidirectional"))
      (node (ref "C56") (pin "2") (pinfunction "2_2") (pintype "bidirectional"))
      (node (ref "CN8") (pin "P$1") (pinfunction "P$1_P$1") (pintype "bidirectional"))
      (node (ref "CN8") (pin "P$2") (pinfunction "P$1_P$2") (pintype "bidirectional"))
      (node (ref "CN8") (pin "P$3") (pinfunction "P$1_P$3") (pintype "bidirectional"))
      (node (ref "D7") (pin "K") (pinfunction "K_K") (pintype "bidirectional"))
      (node (ref "D8") (pin "2") (pinfunction "K_2") (pintype "bidirectional"))
      (node (ref "R37") (pin "2") (pinfunction "2_2") (pintype "bidirectional"))
    )
    (net (code "22") (name "LED3_K") (class "Default")
      (node (ref "CN9") (pin "P$1") (pinfunction "P$1_P$1") (pintype "bidirectional"))
      (node (ref "CN9") (pin "P$2") (pinfunction "P$1_P$2") (pintype "bidirectional"))
      (node (ref "CN9") (pin "P$3") (pinfunction "P$1_P$3") (pintype "bidirectional"))
      (node (ref "D13") (pin "K") (pinfunction "K_K") (pintype "bidirectional"))
      (node (ref "R39") (pin "2") (pinfunction "2_2") (pintype "bidirectional"))
      (node (ref "U10") (pin "9") (pinfunction "FB_9") (pintype "bidirectional"))
    )
    (net (code "23") (name "LED_PWM_0") (class "Default")
      (node (ref "R41") (pin "2") (pinfunction "2_2") (pintype "bidirectional"))
      (node (ref "U10") (pin "4") (pinfunction "EN_4") (pintype "bidirectional"))
      (node (ref "U5") (pin "29") (pinfunction "IO5_29") (pintype "bidirectional"))
    )
    (net (code "24") (name "LED_PWM_1") (class "Default")
      (node (ref "R31") (pin "2") (pinfunction "2_2") (pintype "bidirectional"))
      (node (ref "U5") (pin "30") (pinfunction "IO18_30") (pintype "bidirectional"))
      (node (ref "U8") (pin "4") (pinfunction "EN_4") (pintype "bidirectional"))
    )
    (net (code "25") (name "LED_PWM_2") (class "Default")
      (node (ref "R17") (pin "2") (pinfunction "2_2") (pintype "bidirectional"))
      (node (ref "U3") (pin "4") (pinfunction "EN_4") (pintype "bidirectional"))
      (node (ref "U5") (pin "31") (pinfunction "IO19_31") (pintype "bidirectional"))
    )
    (net (code "26") (name "LED_PWM_3") (class "Default")
      (node (ref "R10") (pin "2") (pinfunction "2_2") (pintype "bidirectional"))
      (node (ref "U2") (pin "4") (pinfunction "EN_4") (pintype "bidirectional"))
      (node (ref "U5") (pin "33") (pinfunction "IO21_33") (pintype "bidirectional"))
    )
    (net (code "27") (name "Net-(CN2-5V)") (class "Default")
      (node (ref "CN2") (pin "VCC") (pinfunction "5V_VCC") (pintype "bidirectional"))
      (node (ref "FB1") (pin "1") (pinfunction "1_1") (pintype "bidirectional"))
    )
    (net (code "28") (name "Net-(D2-PadA)") (class "Default")
      (node (ref "D2") (pin "A") (pinfunction "A_A") (pintype "bidirectional"))
      (node (ref "L2") (pin "2") (pinfunction "2_2") (pintype "bidirectional"))
      (node (ref "U2") (pin "1") (pinfunction "SW_1") (pintype "bidirectional"))
      (node (ref "U2") (pin "2") (pinfunction "SW_2") (pintype "bidirectional"))
    )
    (net (code "29") (name "Net-(D3-PadA)") (class "Default")
      (node (ref "D3") (pin "A") (pinfunction "A_A") (pintype "bidirectional"))
      (node (ref "L3") (pin "2") (pinfunction "2_2") (pintype "bidirectional"))
      (node (ref "U3") (pin "1") (pinfunction "SW_1") (pintype "bidirectional"))
      (node (ref "U3") (pin "2") (pinfunction "SW_2") (pintype "bidirectional"))
    )
    (net (code "30") (name "Net-(D5-PadA)") (class "Default")
      (node (ref "D5") (pin "A") (pinfunction "A_A") (pintype "bidirectional"))
      (node (ref "L5") (pin "2") (pinfunction "2_2") (pintype "bidirectional"))
      (node (ref "U8") (pin "1") (pinfunction "SW_1") (pintype "bidirectional"))
      (node (ref "U8") (pin "2") (pinfunction "SW_2") (pintype "bidirectional"))
    )
    (net (code "31") (name "Net-(D7-PadA)") (class "Default")
      (node (ref "D7") (pin "A") (pinfunction "A_A") (pintype "bidirectional"))
      (node (ref "L7") (pin "2") (pinfunction "2_2") (pintype "bidirectional"))
      (node (ref "U10") (pin "1") (pinfunction "SW_1") (pintype "bidirectional"))
      (node (ref "U10") (pin "2") (pinfunction "SW_2") (pintype "bidirectional"))
    )
    (net (code "32") (name "Net-(Q4-B)") (class "Default")
      (node (ref "Q4") (pin "1") (pinfunction "B_1") (pintype "bidirectional"))
      (node (ref "R21") (pin "1") (pinfunction "1_1") (pintype "bidirectional"))
    )
    (net (code "33") (name "Net-(Q5-B)") (class "Default")
      (node (ref "Q5") (pin "1") (pinfunction "B_1") (pintype "bidirectional"))
      (node (ref "R22") (pin "1") (pinfunction "1_1") (pintype "bidirectional"))
    )
    (net (code "34") (name "Net-(TP1-P$1)") (class "Default")
      (node (ref "D1") (pin "A") (pinfunction "A_A") (pintype "bidirectional"))
      (node (ref "D4") (pin "A") (pinfunction "A_A") (pintype "bidirectional"))
      (node (ref "TP1") (pin "1") (pinfunction "P$1_1") (pintype "bidirectional"))
    )
    (net (code "35") (name "Net-(U1-D+)") (class "Default")
      (node (ref "U1") (pin "4") (pinfunction "D+_4") (pintype "bidirectional"))
      (node (ref "U6") (pin "1") (pinfunction "D+_IN_1") (pintype "bidirectional"))
    )
    (net (code "36") (name "Net-(U1-D-)") (class "Default")
      (node (ref "U1") (pin "5") (pinfunction "D-_5") (pintype "bidirectional"))
      (node (ref "U6") (pin "3") (pinfunction "D-_IN_3") (pintype "bidirectional"))
    )
    (net (code "37") (name "Net-(U1-VBUS)") (class "Default")
      (node (ref "R1") (pin "2") (pinfunction "2_2") (pintype "bidirectional"))
      (node (ref "R2") (pin "2") (pinfunction "2_2") (pintype "bidirectional"))
      (node (ref "U1") (pin "8") (pinfunction "VBUS_8") (pintype "bidirectional"))
    )
    (net (code "38") (name "Net-(U1-VDD)") (class "Default")
      (node (ref "C1") (pin "2") (pinfunction "2_2") (pintype "bidirectional"))
      (node (ref "C2") (pin "2") (pinfunction "2_2") (pintype "bidirectional"))
      (node (ref "U1") (pin "6") (pinfunction "VDD_6") (pintype "bidirectional"))
      (node (ref "U1") (pin "7") (pinfunction "VREGIN_7") (pintype "bidirectional"))
    )
    (net (code "39") (name "Net-(U1-~{RST})") (class "Default")
      (node (ref "R4") (pin "1") (pinfunction "1_1") (pintype "bidirectional"))
      (node (ref "U1") (pin "9") (pinfunction "~{RST}_9") (pintype "bidirectional"))
    )
    (net (code "40") (name "Net-(U1-~{SUSPEND})") (class "Default")
      (node (ref "R3") (pin "2") (pinfunction "2_2") (pintype "bidirectional"))
      (node (ref "U1") (pin "11") (pinfunction "~{SUSPEND}_11") (pintype "bidirectional"))
    )
    (net (code "41") (name "Net-(U2-COMP)") (class "Default")
      (node (ref "C11") (pin "2") (pinfunction "2_2") (pintype "bidirectional"))
      (node (ref "U2") (pin "8") (pinfunction "COMP_8") (pintype "bidirectional"))
    )
    (net (code "42") (name "Net-(U2-DIMC)") (class "Default")
      (node (ref "C18") (pin "2") (pinfunction "2_2") (pintype "bidirectional"))
      (node (ref "U2") (pin "6") (pinfunction "DIMC_6") (pintype "bidirectional"))
    )
    (net (code "43") (name "Net-(U2-FREQ)") (class "Default")
      (node (ref "R9") (pin "2") (pinfunction "2_2") (pintype "bidirectional"))
      (node (ref "U2") (pin "10") (pinfunction "FREQ_10") (pintype "bidirectional"))
    )
    (net (code "44") (name "Net-(U2-OVP)") (class "Default")
      (node (ref "R6") (pin "1") (pinfunction "1_1") (pintype "bidirectional"))
      (node (ref "R7") (pin "2") (pinfunction "2_2") (pintype "bidirectional"))
      (node (ref "U2") (pin "11") (pinfunction "OVP_11") (pintype "bidirectional"))
    )
    (net (code "45") (name "Net-(U2-SS)") (class "Default")
      (node (ref "C10") (pin "2") (pinfunction "2_2") (pintype "bidirectional"))
      (node (ref "U2") (pin "5") (pinfunction "SS_5") (pintype "bidirectional"))
    )
    (net (code "46") (name "Net-(U3-COMP)") (class "Default")
      (node (ref "C25") (pin "2") (pinfunction "2_2") (pintype "bidirectional"))
      (node (ref "U3") (pin "8") (pinfunction "COMP_8") (pintype "bidirectional"))
    )
    (net (code "47") (name "Net-(U3-DIMC)") (class "Default")
      (node (ref "C26") (pin "2") (pinfunction "2_2") (pintype "bidirectional"))
      (node (ref "U3") (pin "6") (pinfunction "DIMC_6") (pintype "bidirectional"))
    )
    (net (code "48") (name "Net-(U3-FREQ)") (class "Default")
      (node (ref "R15") (pin "2") (pinfunction "2_2") (pintype "bidirectional"))
      (node (ref "U3") (pin "10") (pinfunction "FREQ_10") (pintype "bidirectional"))
    )
    (net (code "49") (name "Net-(U3-OVP)") (class "Default")
      (node (ref "R12") (pin "1") (pinfunction "1_1") (pintype "bidirectional"))
      (node (ref "R13") (pin "2") (pinfunction "2_2") (pintype "bidirectional"))
      (node (ref "U3") (pin "11") (pinfunction "OVP_11") (pintype "bidirectional"))
    )
    (net (code "50") (name "Net-(U3-SS)") (class "Default")
      (node (ref "C24") (pin "2") (pinfunction "2_2") (pintype "bidirectional"))
      (node (ref "U3") (pin "5") (pinfunction "SS_5") (pintype "bidirectional"))
    )
    (net (code "51") (name "Net-(U5-IO2)") (class "Default")
      (node (ref "R34") (pin "1") (pinfunction "1_1") (pintype "bidirectional"))
      (node (ref "U5") (pin "24") (pinfunction "IO2_24") (pintype "bidirectional"))
    )
    (net (code "52") (name "Net-(U6-D+_OUT)") (class "Default")
      (node (ref "CN2") (pin "D+") (pinfunction "D+_D+") (pintype "bidirectional"))
      (node (ref "U6") (pin "6") (pinfunction "D+_OUT_6") (pintype "bidirectional"))
    )
    (net (code "53") (name "Net-(U6-D-OUT)") (class "Default")
      (node (ref "CN2") (pin "D-") (pinfunction "D-_D-") (pintype "bidirectional"))
      (node (ref "U6") (pin "4") (pinfunction "D-OUT_4") (pintype "bidirectional"))
    )
    (net (code "54") (name "Net-(U8-COMP)") (class "Default")
      (node (ref "C39") (pin "2") (pinfunction "2_2") (pintype "bidirectional"))
      (node (ref "U8") (pin "8") (pinfunction "COMP_8") (pintype "bidirectional"))
    )
    (net (code "55") (name "Net-(U8-DIMC)") (class "Default")
      (node (ref "C40") (pin "2") (pinfunction "2_2") (pintype "bidirectional"))
      (node (ref "U8") (pin "6") (pinfunction "DIMC_6") (pintype "bidirectional"))
    )
    (net (code "56") (name "Net-(U8-FREQ)") (class "Default")
      (node (ref "R30") (pin "2") (pinfunction "2_2") (pintype "bidirectional"))
      (node (ref "U8") (pin "10") (pinfunction "FREQ_10") (pintype "bidirectional"))
    )
    (net (code "57") (name "Net-(U8-OVP)") (class "Default")
      (node (ref "R27") (pin "1") (pinfunction "1_1") (pintype "bidirectional"))
      (node (ref "R28") (pin "2") (pinfunction "2_2") (pintype "bidirectional"))
      (node (ref "U8") (pin "11") (pinfunction "OVP_11") (pintype "bidirectional"))
    )
    (net (code "58") (name "Net-(U8-SS)") (class "Default")
      (node (ref "C38") (pin "2") (pinfunction "2_2") (pintype "bidirectional"))
      (node (ref "U8") (pin "5") (pinfunction "SS_5") (pintype "bidirectional"))
    )
    (net (code "59") (name "Net-(U10-COMP)") (class "Default")
      (node (ref "C53") (pin "2") (pinfunction "2_2") (pintype "bidirectional"))
      (node (ref "U10") (pin "8") (pinfunction "COMP_8") (pintype "bidirectional"))
    )
    (net (code "60") (name "Net-(U10-DIMC)") (class "Default")
      (node (ref "C54") (pin "2") (pinfunction "2_2") (pintype "bidirectional"))
      (node (ref "U10") (pin "6") (pinfunction "DIMC_6") (pintype "bidirectional"))
    )
    (net (code "61") (name "Net-(U10-FREQ)") (class "Default")
      (node (ref "R40") (pin "2") (pinfunction "2_2") (pintype "bidirectional"))
      (node (ref "U10") (pin "10") (pinfunction "FREQ_10") (pintype "bidirectional"))
    )
    (net (code "62") (name "Net-(U10-OVP)") (class "Default")
      (node (ref "R37") (pin "1") (pinfunction "1_1") (pintype "bidirectional"))
      (node (ref "R38") (pin "2") (pinfunction "2_2") (pintype "bidirectional"))
      (node (ref "U10") (pin "11") (pinfunction "OVP_11") (pintype "bidirectional"))
    )
    (net (code "63") (name "Net-(U10-SS)") (class "Default")
      (node (ref "C52") (pin "2") (pinfunction "2_2") (pintype "bidirectional"))
      (node (ref "U10") (pin "5") (pinfunction "SS_5") (pintype "bidirectional"))
    )
    (net (code "64") (name "RS485_A") (class "Default")
      (node (ref "R18") (pin "2") (pinfunction "2_2") (pintype "bidirectional"))
      (node (ref "TP3") (pin "1") (pinfunction "P$1_1") (pintype "bidirectional"))
      (node (ref "U4") (pin "6") (pinfunction "A_6") (pintype "bidirectional"))
    )
    (net (code "65") (name "RS485_B") (class "Default")
      (node (ref "R18") (pin "1") (pinfunction "1_1") (pintype "bidirectional"))
      (node (ref "TP4") (pin "1") (pinfunction "P$1_1") (pintype "bidirectional"))
      (node (ref "U4") (pin "7") (pinfunction "B_7") (pintype "bidirectional"))
    )
    (net (code "66") (name "VIN") (class "Default")
      (node (ref "C19") (pin "2") (pinfunction "2_2") (pintype "bidirectional"))
      (node (ref "C23") (pin "2") (pinfunction "2_2") (pintype "bidirectional"))
      (node (ref "C27") (pin "2") (pinfunction "2_2") (pintype "bidirectional"))
      (node (ref "C31") (pin "2") (pinfunction "2_2") (pintype "bidirectional"))
      (node (ref "C37") (pin "2") (pinfunction "2_2") (pintype "bidirectional"))
      (node (ref "C41") (pin "2") (pinfunction "2_2") (pintype "bidirectional"))
      (node (ref "C51") (pin "2") (pinfunction "2_2") (pintype "bidirectional"))
      (node (ref "C55") (pin "2") (pinfunction "2_2") (pintype "bidirectional"))
      (node (ref "C7") (pin "2") (pinfunction "2_2") (pintype "bidirectional"))
      (node (ref "C9") (pin "2") (pinfunction "2_2") (pintype "bidirectional"))
      (node (ref "D1") (pin "K") (pinfunction "K_K") (pintype "bidirectional"))
      (node (ref "D4") (pin "K") (pinfunction "K_K") (pintype "bidirectional"))
      (node (ref "D6") (pin "K") (pinfunction "K_K") (pintype "bidirectional"))
      (node (ref "D9") (pin "K") (pinfunction "K_K") (pintype "bidirectional"))
      (node (ref "L2") (pin "1") (pinfunction "1_1") (pintype "bidirectional"))
      (node (ref "L3") (pin "1") (pinfunction "1_1") (pintype "bidirectional"))
      (node (ref "L5") (pin "1") (pinfunction "1_1") (pintype "bidirectional"))
      (node (ref "L7") (pin "1") (pinfunction "1_1") (pintype "bidirectional"))
      (node (ref "U10") (pin "3") (pinfunction "VIN_3") (pintype "bidirectional"))
      (node (ref "U11") (pin "3") (pinfunction "VIN_3") (pintype "bidirectional"))
      (node (ref "U11") (pin "4") (pinfunction "EN_4") (pintype "bidirectional"))
      (node (ref "U2") (pin "3") (pinfunction "VIN_3") (pintype "bidirectional"))
      (node (ref "U3") (pin "3") (pinfunction "VIN_3") (pintype "bidirectional"))
      (node (ref "U8") (pin "3") (pinfunction "VIN_3") (pintype "bidirectional"))
    )
    (net (code "67") (name "unconnected-(CN2-PadID)") (class "Default")
      (node (ref "CN2") (pin "ID") (pinfunction "ID_ID") (pintype "bidirectional"))
    )
    (net (code "68") (name "unconnected-(U1-CHR0-Pad15)") (class "Default")
      (node (ref "U1") (pin "15") (pinfunction "CHR0_15") (pintype "bidirectional"))
    )
    (net (code "69") (name "unconnected-(U1-CHR1-Pad14)") (class "Default")
      (node (ref "U1") (pin "14") (pinfunction "CHR1_14") (pintype "bidirectional"))
    )
    (net (code "70") (name "unconnected-(U1-CHREN-Pad13)") (class "Default")
      (node (ref "U1") (pin "13") (pinfunction "CHREN_13") (pintype "bidirectional"))
    )
    (net (code "71") (name "unconnected-(U1-CTS-Pad23)") (class "Default")
      (node (ref "U1") (pin "23") (pinfunction "CTS_23") (pintype "bidirectional"))
    )
    (net (code "72") (name "unconnected-(U1-DCD-Pad1)") (class "Default")
      (node (ref "U1") (pin "1") (pinfunction "DCD_1") (pintype "bidirectional"))
    )
    (net (code "73") (name "unconnected-(U1-DSR-Pad27)") (class "Default")
      (node (ref "U1") (pin "27") (pinfunction "DSR_27") (pintype "bidirectional"))
    )
    (net (code "74") (name "unconnected-(U1-GPIO0{slash}TXT-Pad19)") (class "Default")
      (node (ref "U1") (pin "19") (pinfunction "GPIO0/TXT_19") (pintype "bidirectional"))
    )
    (net (code "75") (name "unconnected-(U1-GPIO1{slash}RXT-Pad18)") (class "Default")
      (node (ref "U1") (pin "18") (pinfunction "GPIO1/RXT_18") (pintype "bidirectional"))
    )
    (net (code "76") (name "unconnected-(U1-GPIO2{slash}RS485-Pad17)") (class "Default")
      (node (ref "U1") (pin "17") (pinfunction "GPIO2/RS485_17") (pintype "bidirectional"))
    )
    (net (code "77") (name "unconnected-(U1-GPIO3{slash}WKUP-Pad16)") (class "Default")
      (node (ref "U1") (pin "16") (pinfunction "GPIO3/WKUP_16") (pintype "bidirectional"))
    )
    (net (code "78") (name "unconnected-(U1-GPIO4-Pad22)") (class "Default")
      (node (ref "U1") (pin "22") (pinfunction "GPIO4_22") (pintype "bidirectional"))
    )
    (net (code "79") (name "unconnected-(U1-GPIO5-Pad21)") (class "Default")
      (node (ref "U1") (pin "21") (pinfunction "GPIO5_21") (pintype "bidirectional"))
    )
    (net (code "80") (name "unconnected-(U1-GPIO6-Pad20)") (class "Default")
      (node (ref "U1") (pin "20") (pinfunction "GPIO6_20") (pintype "bidirectional"))
    )
    (net (code "81") (name "unconnected-(U1-RI{slash}CLK-Pad2)") (class "Default")
      (node (ref "U1") (pin "2") (pinfunction "RI/CLK_2") (pintype "bidirectional"))
    )
    (net (code "82") (name "unconnected-(U1-SUSPEND-Pad12)") (class "Default")
      (node (ref "U1") (pin "12") (pinfunction "SUSPEND_12") (pintype "bidirectional"))
    )
    (net (code "83") (name "unconnected-(U5-IO12-Pad14)") (class "Default")
      (node (ref "U5") (pin "14") (pinfunction "IO12_14") (pintype "bidirectional"))
    )
    (net (code "84") (name "unconnected-(U5-IO14-Pad13)") (class "Default")
      (node (ref "U5") (pin "13") (pinfunction "IO14_13") (pintype "bidirectional"))
    )
    (net (code "85") (name "unconnected-(U5-IO22-Pad36)") (class "Default")
      (node (ref "U5") (pin "36") (pinfunction "IO22_36") (pintype "bidirectional"))
    )
    (net (code "86") (name "unconnected-(U5-IO23-Pad37)") (class "Default")
      (node (ref "U5") (pin "37") (pinfunction "IO23_37") (pintype "bidirectional"))
    )
    (net (code "87") (name "unconnected-(U5-IO25-Pad10)") (class "Default")
      (node (ref "U5") (pin "10") (pinfunction "IO25_10") (pintype "bidirectional"))
    )
    (net (code "88") (name "unconnected-(U5-IO26-Pad11)") (class "Default")
      (node (ref "U5") (pin "11") (pinfunction "IO26_11") (pintype "bidirectional"))
    )
    (net (code "89") (name "unconnected-(U5-IO27-Pad12)") (class "Default")
      (node (ref "U5") (pin "12") (pinfunction "IO27_12") (pintype "bidirectional"))
    )
    (net (code "90") (name "unconnected-(U5-IO32-Pad8)") (class "Default")
      (node (ref "U5") (pin "8") (pinfunction "IO32_8") (pintype "bidirectional"))
    )
    (net (code "91") (name "unconnected-(U5-IO33-Pad9)") (class "Default")
      (node (ref "U5") (pin "9") (pinfunction "IO33_9") (pintype "bidirectional"))
    )
    (net (code "92") (name "unconnected-(U5-IO34-Pad6)") (class "Default")
      (node (ref "U5") (pin "6") (pinfunction "IO34_6") (pintype "bidirectional"))
    )
    (net (code "93") (name "unconnected-(U5-IO35-Pad7)") (class "Default")
      (node (ref "U5") (pin "7") (pinfunction "IO35_7") (pintype "bidirectional"))
    )
    (net (code "94") (name "unconnected-(U5-SCK{slash}CLK-Pad20)") (class "Default")
      (node (ref "U5") (pin "20") (pinfunction "SCK/CLK_20") (pintype "bidirectional"))
    )
    (net (code "95") (name "unconnected-(U5-SCS{slash}CMD-Pad19)") (class "Default")
      (node (ref "U5") (pin "19") (pinfunction "SCS/CMD_19") (pintype "bidirectional"))
    )
    (net (code "96") (name "unconnected-(U5-SDI{slash}SD1-Pad22)") (class "Default")
      (node (ref "U5") (pin "22") (pinfunction "SDI/SD1_22") (pintype "bidirectional"))
    )
    (net (code "97") (name "unconnected-(U5-SDO{slash}SD0-Pad21)") (class "Default")
      (node (ref "U5") (pin "21") (pinfunction "SDO/SD0_21") (pintype "bidirectional"))
    )
    (net (code "98") (name "unconnected-(U5-SENSOR_VN-Pad5)") (class "Default")
      (node (ref "U5") (pin "5") (pinfunction "SENSOR_VN_5") (pintype "bidirectional"))
    )
    (net (code "99") (name "unconnected-(U5-SENSOR_VP-Pad4)") (class "Default")
      (node (ref "U5") (pin "4") (pinfunction "SENSOR_VP_4") (pintype "bidirectional"))
    )
    (net (code "100") (name "unconnected-(U5-SHD{slash}SD2-Pad17)") (class "Default")
      (node (ref "U5") (pin "17") (pinfunction "SHD/SD2_17") (pintype "bidirectional"))
    )
    (net (code "101") (name "unconnected-(U5-SWP{slash}SD3-Pad18)") (class "Default")
      (node (ref "U5") (pin "18") (pinfunction "SWP/SD3_18") (pintype "bidirectional"))
    )
    (net (code "102") (name "unconnected-(U11-PGOOD-Pad5)") (class "Default")
      (node (ref "U11") (pin "5") (pinfunction "PGOOD_5") (pintype "bidirectional"))
    )
  )
)
